# 13-Counter74LS90.net
KiCad netlist of a schematic drawn in Altium Designer
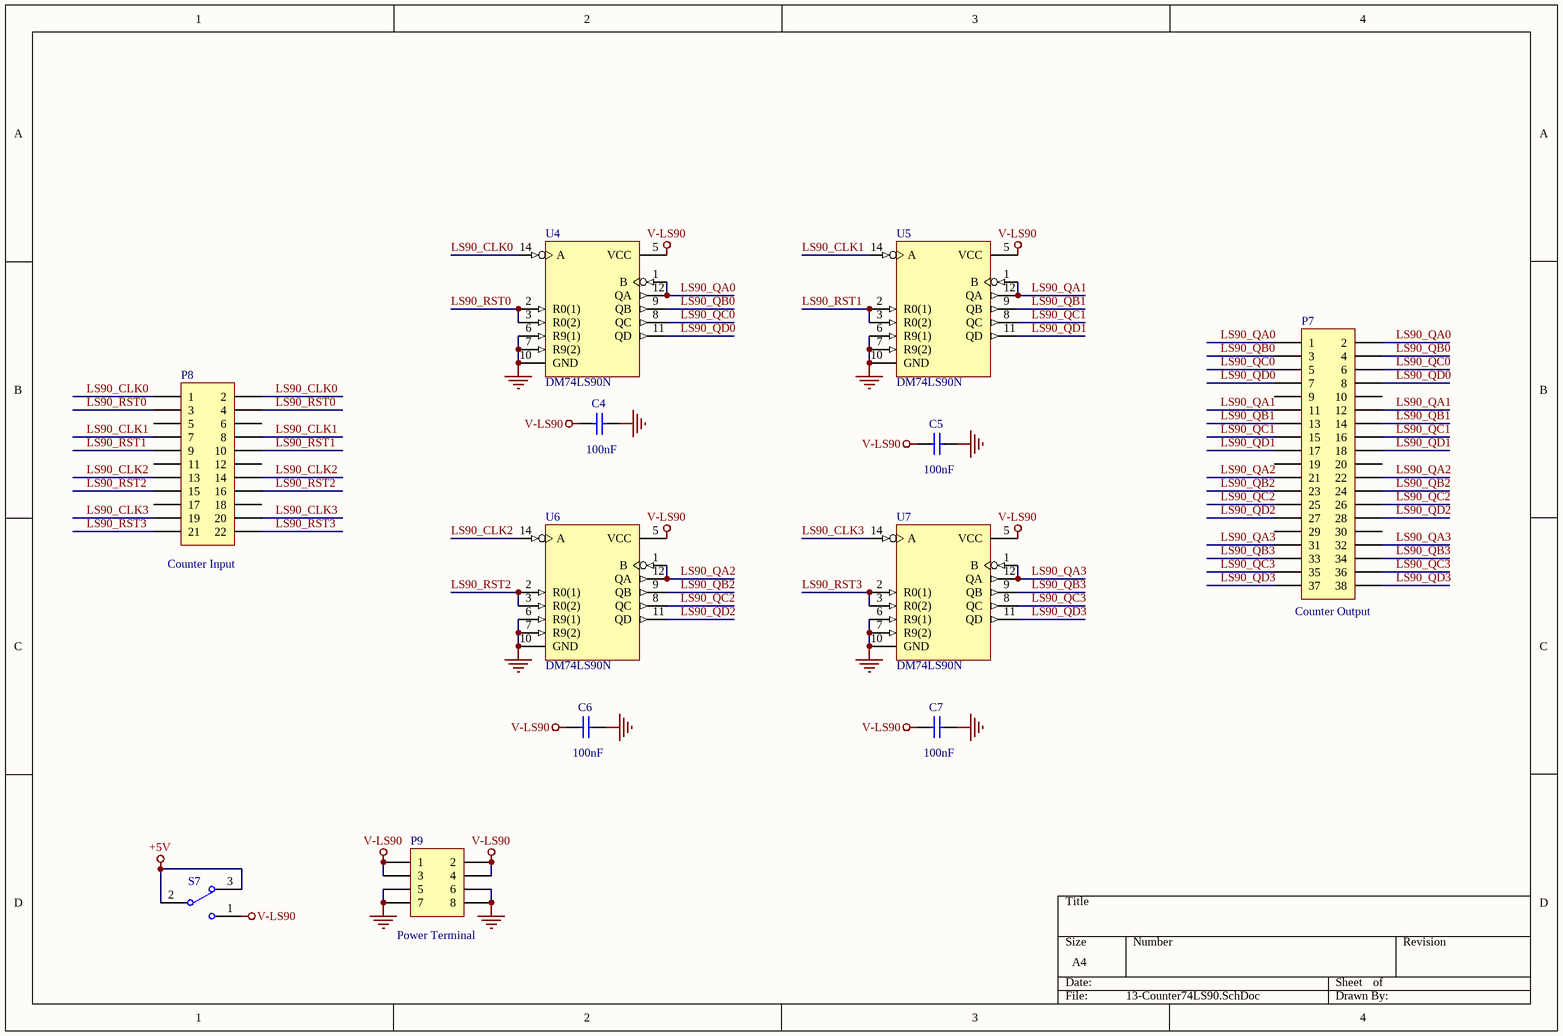
[diagram p0: 13-Counter74LS90.SchDoc]

(export (version "E")
  (design (tool "Eeschema 10.0.6"))
  (components
    (comp (ref "C4")
      (value "100nF")
      (footprint "c-0805")
      (description "Capacitor")
      (fields (field (name "Comment") "104") (field (name "PUBLISHER") "Altium Limited"))
      (libsource (lib "Miscellaneous Devices") (part "Cap"))
    )
    (comp (ref "C5")
      (value "100nF")
      (footprint "c-0805")
      (description "Capacitor")
      (fields (field (name "Comment") "104") (field (name "PUBLISHER") "Altium Limited"))
      (libsource (lib "Miscellaneous Devices") (part "Cap"))
    )
    (comp (ref "C6")
      (value "100nF")
      (footprint "c-0805")
      (description "Capacitor")
      (fields (field (name "Comment") "104") (field (name "PUBLISHER") "Altium Limited"))
      (libsource (lib "Miscellaneous Devices") (part "Cap"))
    )
    (comp (ref "C7")
      (value "100nF")
      (footprint "c-0805")
      (description "Capacitor")
      (fields (field (name "Comment") "104") (field (name "PUBLISHER") "Altium Limited"))
      (libsource (lib "Miscellaneous Devices") (part "Cap"))
    )
    (comp (ref "P7")
      (value "Counter Output")
      (footprint "HDR2X19")
      (description "Header, 19-Pin, Dual row")
      (fields (field (name "Comment") "Header 19X2"))
      (libsource (lib "Miscellaneous Connectors") (part "Header 19X2"))
    )
    (comp (ref "P8")
      (value "Counter Input")
      (footprint "HDR2X11")
      (description "Header, 11-Pin, Dual row")
      (fields (field (name "Comment") "Header 11X2"))
      (libsource (lib "Miscellaneous Connectors") (part "Header 11X2"))
    )
    (comp (ref "P9")
      (value "Header 4X2")
      (footprint "HDR2X4")
      (description "Header, 4-Pin, Dual row")
      (fields (field (name "PUBLISHER") "Power Terminal"))
      (libsource (lib "Miscellaneous Connectors") (part "Header 4X2"))
    )
    (comp (ref "S7")
      (value "SW-SPDT")
      (footprint "SW-DIP1SMD")
      (description "SPDT Subminiature Toggle Switch, Right Angle Mounting, Vertical Actuation")
      (fields (field (name "PUBLISHER") "Altium Limited"))
      (libsource (lib "Miscellaneous Devices") (part "SW-SPDT"))
    )
    (comp (ref "U4")
      (value "DM74LS90N")
      (footprint "SK-DIP14-300")
      (description "Decade and Binary Counter")
      (fields (field (name "PUBLISHER") "Altium Limited"))
      (libsource (lib "FSC Logic Counter") (part "DM74LS90N"))
    )
    (comp (ref "U5")
      (value "DM74LS90N")
      (footprint "SK-DIP14-300")
      (description "Decade and Binary Counter")
      (fields (field (name "PUBLISHER") "Altium Limited"))
      (libsource (lib "FSC Logic Counter") (part "DM74LS90N"))
    )
    (comp (ref "U6")
      (value "DM74LS90N")
      (footprint "SK-DIP14-300")
      (description "Decade and Binary Counter")
      (fields (field (name "PUBLISHER") "Altium Limited"))
      (libsource (lib "FSC Logic Counter") (part "DM74LS90N"))
    )
    (comp (ref "U7")
      (value "DM74LS90N")
      (footprint "SK-DIP14-300")
      (description "Decade and Binary Counter")
      (fields (field (name "PUBLISHER") "Altium Limited"))
      (libsource (lib "FSC Logic Counter") (part "DM74LS90N"))
    )
  )
  (nets
    (net (code "1") (name "+5V") (class "Default")
      (node (ref "S7") (pin "2") (pinfunction "2_2") (pintype "passive"))
      (node (ref "S7") (pin "3") (pinfunction "3_3") (pintype "passive"))
    )
    (net (code "2") (name "/LS90_CLK0") (class "Default")
      (node (ref "P8") (pin "1") (pinfunction "1_1") (pintype "passive"))
      (node (ref "P8") (pin "2") (pinfunction "2_2") (pintype "passive"))
      (node (ref "U4") (pin "14") (pinfunction "A_14") (pintype "input"))
    )
    (net (code "3") (name "/LS90_CLK1") (class "Default")
      (node (ref "P8") (pin "7") (pinfunction "7_7") (pintype "passive"))
      (node (ref "P8") (pin "8") (pinfunction "8_8") (pintype "passive"))
      (node (ref "U5") (pin "14") (pinfunction "A_14") (pintype "input"))
    )
    (net (code "4") (name "/LS90_CLK2") (class "Default")
      (node (ref "P8") (pin "13") (pinfunction "13_13") (pintype "passive"))
      (node (ref "P8") (pin "14") (pinfunction "14_14") (pintype "passive"))
      (node (ref "U6") (pin "14") (pinfunction "A_14") (pintype "input"))
    )
    (net (code "5") (name "/LS90_CLK3") (class "Default")
      (node (ref "P8") (pin "19") (pinfunction "19_19") (pintype "passive"))
      (node (ref "P8") (pin "20") (pinfunction "20_20") (pintype "passive"))
      (node (ref "U7") (pin "14") (pinfunction "A_14") (pintype "input"))
    )
    (net (code "6") (name "/LS90_QA0") (class "Default")
      (node (ref "P7") (pin "1") (pinfunction "1_1") (pintype "passive"))
      (node (ref "P7") (pin "2") (pinfunction "2_2") (pintype "passive"))
      (node (ref "U4") (pin "1") (pinfunction "B_1") (pintype "input"))
      (node (ref "U4") (pin "12") (pinfunction "QA_12") (pintype "output"))
    )
    (net (code "7") (name "/LS90_QA1") (class "Default")
      (node (ref "P7") (pin "11") (pinfunction "11_11") (pintype "passive"))
      (node (ref "P7") (pin "12") (pinfunction "12_12") (pintype "passive"))
      (node (ref "U5") (pin "1") (pinfunction "B_1") (pintype "input"))
      (node (ref "U5") (pin "12") (pinfunction "QA_12") (pintype "output"))
    )
    (net (code "8") (name "/LS90_QA2") (class "Default")
      (node (ref "P7") (pin "21") (pinfunction "21_21") (pintype "passive"))
      (node (ref "P7") (pin "22") (pinfunction "22_22") (pintype "passive"))
      (node (ref "U6") (pin "1") (pinfunction "B_1") (pintype "input"))
      (node (ref "U6") (pin "12") (pinfunction "QA_12") (pintype "output"))
    )
    (net (code "9") (name "/LS90_QA3") (class "Default")
      (node (ref "P7") (pin "31") (pinfunction "31_31") (pintype "passive"))
      (node (ref "P7") (pin "32") (pinfunction "32_32") (pintype "passive"))
      (node (ref "U7") (pin "1") (pinfunction "B_1") (pintype "input"))
      (node (ref "U7") (pin "12") (pinfunction "QA_12") (pintype "output"))
    )
    (net (code "10") (name "/LS90_QB0") (class "Default")
      (node (ref "P7") (pin "3") (pinfunction "3_3") (pintype "passive"))
      (node (ref "P7") (pin "4") (pinfunction "4_4") (pintype "passive"))
      (node (ref "U4") (pin "9") (pinfunction "QB_9") (pintype "output"))
    )
    (net (code "11") (name "/LS90_QB1") (class "Default")
      (node (ref "P7") (pin "13") (pinfunction "13_13") (pintype "passive"))
      (node (ref "P7") (pin "14") (pinfunction "14_14") (pintype "passive"))
      (node (ref "U5") (pin "9") (pinfunction "QB_9") (pintype "output"))
    )
    (net (code "12") (name "/LS90_QB2") (class "Default")
      (node (ref "P7") (pin "23") (pinfunction "23_23") (pintype "passive"))
      (node (ref "P7") (pin "24") (pinfunction "24_24") (pintype "passive"))
      (node (ref "U6") (pin "9") (pinfunction "QB_9") (pintype "output"))
    )
    (net (code "13") (name "/LS90_QB3") (class "Default")
      (node (ref "P7") (pin "33") (pinfunction "33_33") (pintype "passive"))
      (node (ref "P7") (pin "34") (pinfunction "34_34") (pintype "passive"))
      (node (ref "U7") (pin "9") (pinfunction "QB_9") (pintype "output"))
    )
    (net (code "14") (name "/LS90_QC0") (class "Default")
      (node (ref "P7") (pin "5") (pinfunction "5_5") (pintype "passive"))
      (node (ref "P7") (pin "6") (pinfunction "6_6") (pintype "passive"))
      (node (ref "U4") (pin "8") (pinfunction "QC_8") (pintype "output"))
    )
    (net (code "15") (name "/LS90_QC1") (class "Default")
      (node (ref "P7") (pin "15") (pinfunction "15_15") (pintype "passive"))
      (node (ref "P7") (pin "16") (pinfunction "16_16") (pintype "passive"))
      (node (ref "U5") (pin "8") (pinfunction "QC_8") (pintype "output"))
    )
    (net (code "16") (name "/LS90_QC2") (class "Default")
      (node (ref "P7") (pin "25") (pinfunction "25_25") (pintype "passive"))
      (node (ref "P7") (pin "26") (pinfunction "26_26") (pintype "passive"))
      (node (ref "U6") (pin "8") (pinfunction "QC_8") (pintype "output"))
    )
    (net (code "17") (name "/LS90_QC3") (class "Default")
      (node (ref "P7") (pin "35") (pinfunction "35_35") (pintype "passive"))
      (node (ref "P7") (pin "36") (pinfunction "36_36") (pintype "passive"))
      (node (ref "U7") (pin "8") (pinfunction "QC_8") (pintype "output"))
    )
    (net (code "18") (name "/LS90_QD0") (class "Default")
      (node (ref "P7") (pin "7") (pinfunction "7_7") (pintype "passive"))
      (node (ref "P7") (pin "8") (pinfunction "8_8") (pintype "passive"))
      (node (ref "U4") (pin "11") (pinfunction "QD_11") (pintype "output"))
    )
    (net (code "19") (name "/LS90_QD1") (class "Default")
      (node (ref "P7") (pin "17") (pinfunction "17_17") (pintype "passive"))
      (node (ref "P7") (pin "18") (pinfunction "18_18") (pintype "passive"))
      (node (ref "U5") (pin "11") (pinfunction "QD_11") (pintype "output"))
    )
    (net (code "20") (name "/LS90_QD2") (class "Default")
      (node (ref "P7") (pin "27") (pinfunction "27_27") (pintype "passive"))
      (node (ref "P7") (pin "28") (pinfunction "28_28") (pintype "passive"))
      (node (ref "U6") (pin "11") (pinfunction "QD_11") (pintype "output"))
    )
    (net (code "21") (name "/LS90_QD3") (class "Default")
      (node (ref "P7") (pin "37") (pinfunction "37_37") (pintype "passive"))
      (node (ref "P7") (pin "38") (pinfunction "38_38") (pintype "passive"))
      (node (ref "U7") (pin "11") (pinfunction "QD_11") (pintype "output"))
    )
    (net (code "22") (name "/LS90_RST0") (class "Default")
      (node (ref "P8") (pin "3") (pinfunction "3_3") (pintype "passive"))
      (node (ref "P8") (pin "4") (pinfunction "4_4") (pintype "passive"))
      (node (ref "U4") (pin "2") (pinfunction "R0(1)_2") (pintype "input"))
      (node (ref "U4") (pin "3") (pinfunction "R0(2)_3") (pintype "input"))
    )
    (net (code "23") (name "/LS90_RST1") (class "Default")
      (node (ref "P8") (pin "10") (pinfunction "10_10") (pintype "passive"))
      (node (ref "P8") (pin "9") (pinfunction "9_9") (pintype "passive"))
      (node (ref "U5") (pin "2") (pinfunction "R0(1)_2") (pintype "input"))
      (node (ref "U5") (pin "3") (pinfunction "R0(2)_3") (pintype "input"))
    )
    (net (code "24") (name "/LS90_RST2") (class "Default")
      (node (ref "P8") (pin "15") (pinfunction "15_15") (pintype "passive"))
      (node (ref "P8") (pin "16") (pinfunction "16_16") (pintype "passive"))
      (node (ref "U6") (pin "2") (pinfunction "R0(1)_2") (pintype "input"))
      (node (ref "U6") (pin "3") (pinfunction "R0(2)_3") (pintype "input"))
    )
    (net (code "25") (name "/LS90_RST3") (class "Default")
      (node (ref "P8") (pin "21") (pinfunction "21_21") (pintype "passive"))
      (node (ref "P8") (pin "22") (pinfunction "22_22") (pintype "passive"))
      (node (ref "U7") (pin "2") (pinfunction "R0(1)_2") (pintype "input"))
      (node (ref "U7") (pin "3") (pinfunction "R0(2)_3") (pintype "input"))
    )
    (net (code "26") (name "GND") (class "Default")
      (node (ref "C4") (pin "2") (pinfunction "2_2") (pintype "passive"))
      (node (ref "C5") (pin "2") (pinfunction "2_2") (pintype "passive"))
      (node (ref "C6") (pin "2") (pinfunction "2_2") (pintype "passive"))
      (node (ref "C7") (pin "2") (pinfunction "2_2") (pintype "passive"))
      (node (ref "P9") (pin "5") (pinfunction "5_5") (pintype "passive"))
      (node (ref "P9") (pin "6") (pinfunction "6_6") (pintype "passive"))
      (node (ref "P9") (pin "7") (pinfunction "7_7") (pintype "passive"))
      (node (ref "P9") (pin "8") (pinfunction "8_8") (pintype "passive"))
      (node (ref "U4") (pin "10") (pinfunction "GND_10") (pintype "power_in"))
      (node (ref "U4") (pin "6") (pinfunction "R9(1)_6") (pintype "input"))
      (node (ref "U4") (pin "7") (pinfunction "R9(2)_7") (pintype "input"))
      (node (ref "U5") (pin "10") (pinfunction "GND_10") (pintype "power_in"))
      (node (ref "U5") (pin "6") (pinfunction "R9(1)_6") (pintype "input"))
      (node (ref "U5") (pin "7") (pinfunction "R9(2)_7") (pintype "input"))
      (node (ref "U6") (pin "10") (pinfunction "GND_10") (pintype "power_in"))
      (node (ref "U6") (pin "6") (pinfunction "R9(1)_6") (pintype "input"))
      (node (ref "U6") (pin "7") (pinfunction "R9(2)_7") (pintype "input"))
      (node (ref "U7") (pin "10") (pinfunction "GND_10") (pintype "power_in"))
      (node (ref "U7") (pin "6") (pinfunction "R9(1)_6") (pintype "input"))
      (node (ref "U7") (pin "7") (pinfunction "R9(2)_7") (pintype "input"))
    )
    (net (code "27") (name "V-LS90") (class "Default")
      (node (ref "C4") (pin "1") (pinfunction "1_1") (pintype "passive"))
      (node (ref "C5") (pin "1") (pinfunction "1_1") (pintype "passive"))
      (node (ref "C6") (pin "1") (pinfunction "1_1") (pintype "passive"))
      (node (ref "C7") (pin "1") (pinfunction "1_1") (pintype "passive"))
      (node (ref "P9") (pin "1") (pinfunction "1_1") (pintype "passive"))
      (node (ref "P9") (pin "2") (pinfunction "2_2") (pintype "passive"))
      (node (ref "P9") (pin "3") (pinfunction "3_3") (pintype "passive"))
      (node (ref "P9") (pin "4") (pinfunction "4_4") (pintype "passive"))
      (node (ref "S7") (pin "1") (pinfunction "1_1") (pintype "passive"))
      (node (ref "U4") (pin "5") (pinfunction "VCC_5") (pintype "power_in"))
      (node (ref "U5") (pin "5") (pinfunction "VCC_5") (pintype "power_in"))
      (node (ref "U6") (pin "5") (pinfunction "VCC_5") (pintype "power_in"))
      (node (ref "U7") (pin "5") (pinfunction "VCC_5") (pintype "power_in"))
    )
    (net (code "28") (name "unconnected-(P7-Pad9)") (class "Default")
      (node (ref "P7") (pin "9") (pinfunction "9_9") (pintype "passive"))
    )
    (net (code "29") (name "unconnected-(P7-Pad10)") (class "Default")
      (node (ref "P7") (pin "10") (pinfunction "10_10") (pintype "passive"))
    )
    (net (code "30") (name "unconnected-(P7-Pad19)") (class "Default")
      (node (ref "P7") (pin "19") (pinfunction "19_19") (pintype "passive"))
    )
    (net (code "31") (name "unconnected-(P7-Pad20)") (class "Default")
      (node (ref "P7") (pin "20") (pinfunction "20_20") (pintype "passive"))
    )
    (net (code "32") (name "unconnected-(P7-Pad29)") (class "Default")
      (node (ref "P7") (pin "29") (pinfunction "29_29") (pintype "passive"))
    )
    (net (code "33") (name "unconnected-(P7-Pad30)") (class "Default")
      (node (ref "P7") (pin "30") (pinfunction "30_30") (pintype "passive"))
    )
    (net (code "34") (name "unconnected-(P8-Pad5)") (class "Default")
      (node (ref "P8") (pin "5") (pinfunction "5_5") (pintype "passive"))
    )
    (net (code "35") (name "unconnected-(P8-Pad6)") (class "Default")
      (node (ref "P8") (pin "6") (pinfunction "6_6") (pintype "passive"))
    )
    (net (code "36") (name "unconnected-(P8-Pad11)") (class "Default")
      (node (ref "P8") (pin "11") (pinfunction "11_11") (pintype "passive"))
    )
    (net (code "37") (name "unconnected-(P8-Pad12)") (class "Default")
      (node (ref "P8") (pin "12") (pinfunction "12_12") (pintype "passive"))
    )
    (net (code "38") (name "unconnected-(P8-Pad17)") (class "Default")
      (node (ref "P8") (pin "17") (pinfunction "17_17") (pintype "passive"))
    )
    (net (code "39") (name "unconnected-(P8-Pad18)") (class "Default")
      (node (ref "P8") (pin "18") (pinfunction "18_18") (pintype "passive"))
    )
  )
)
